# TurntableStrobeModule.net
KiCad netlist of a schematic drawn in EAGLE
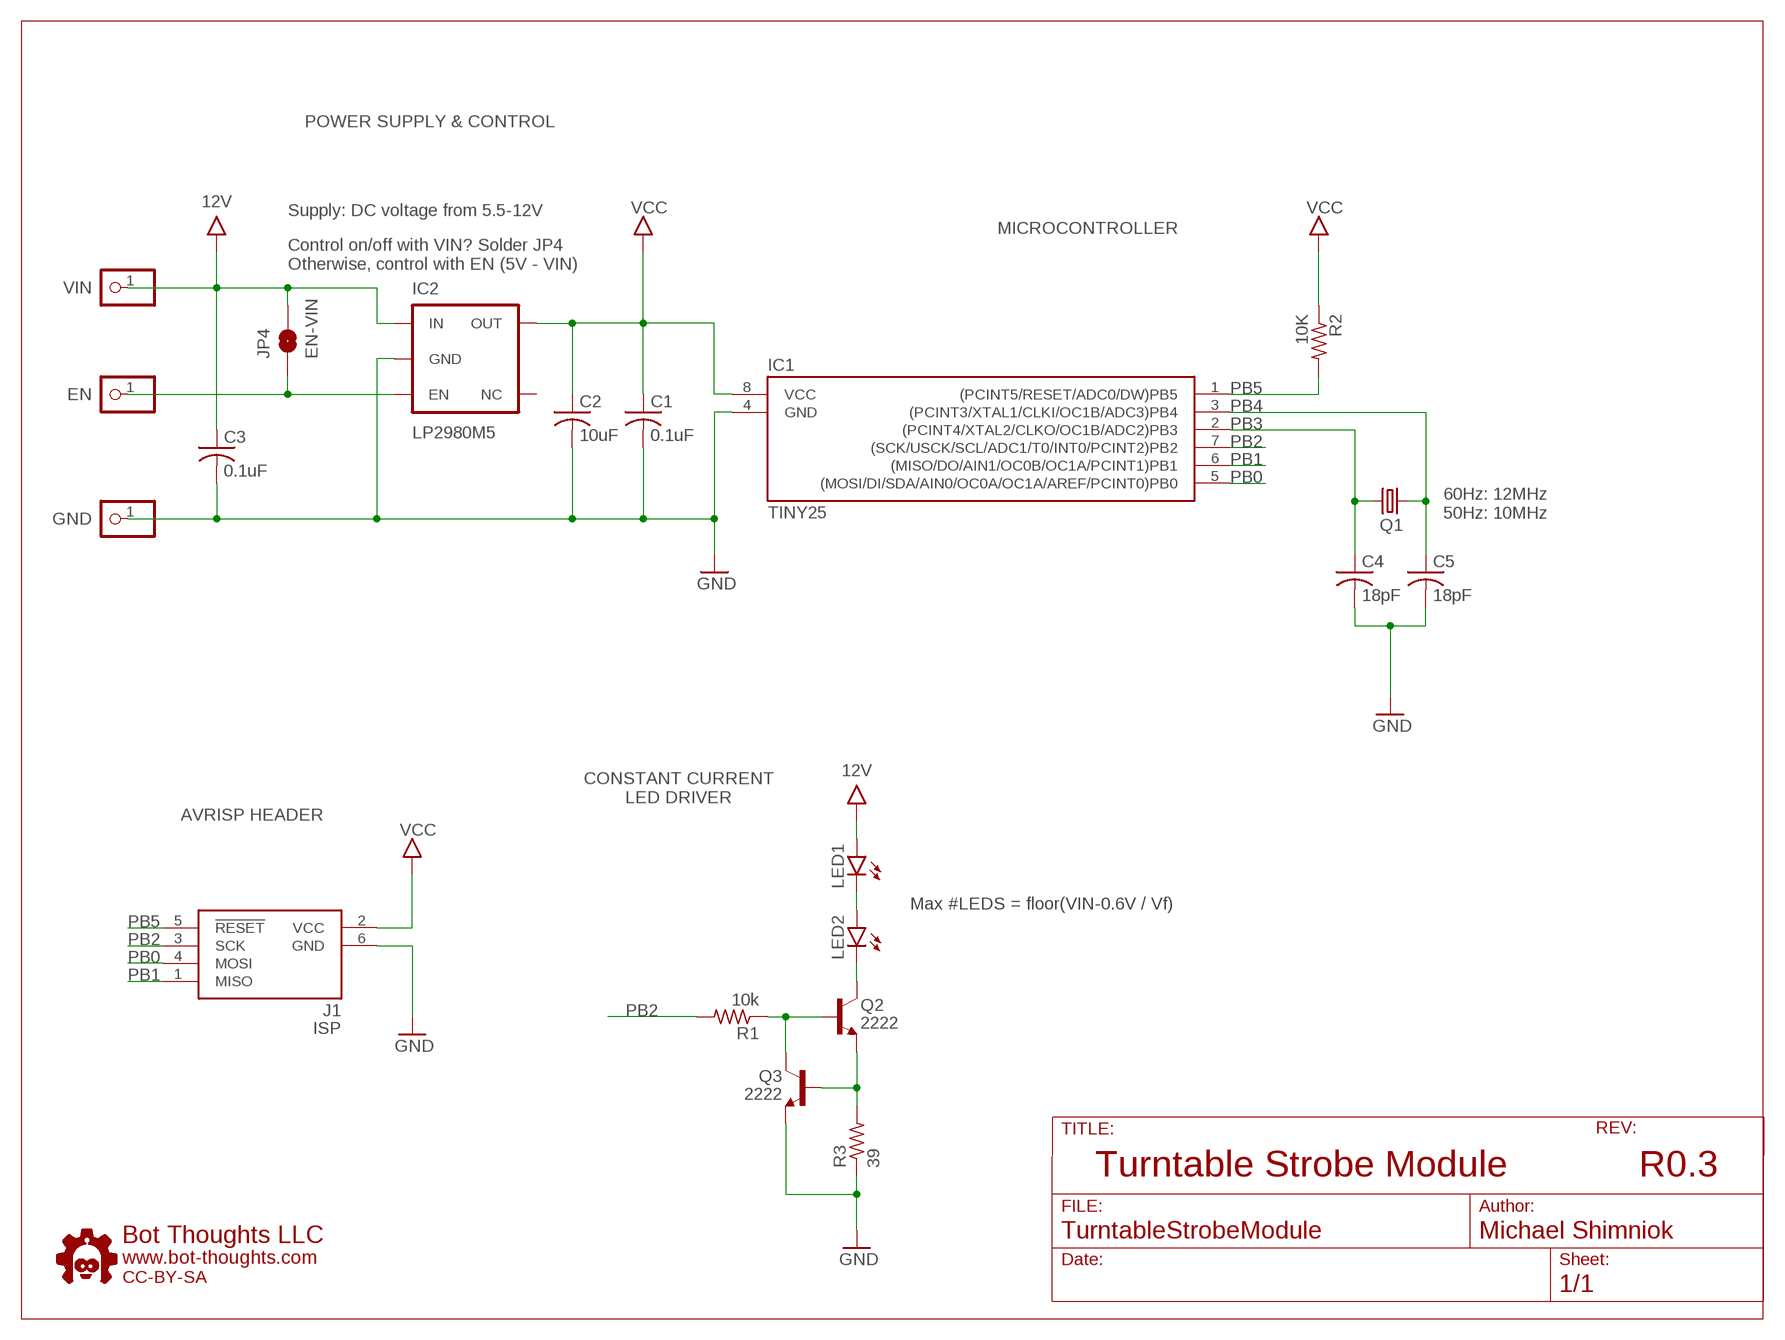
[diagram p0: schematic, sheet 1]

(export (version "E")
  (design (tool "Eeschema 10.0.6"))
  (components
    (comp (ref "C1")
      (value "0.1uF")
      (footprint "eagle-import:0603")
      (libsource (lib "eagle-import") (part "C-0603"))
    )
    (comp (ref "C2")
      (value "10uF")
      (footprint "eagle-import:1206")
      (libsource (lib "eagle-import") (part "C-1206"))
    )
    (comp (ref "C3")
      (value "0.1uF")
      (footprint "eagle-import:0603")
      (libsource (lib "eagle-import") (part "C-0603"))
    )
    (comp (ref "C4")
      (value "18pF")
      (footprint "eagle-import:0603")
      (libsource (lib "eagle-import") (part "C-0603"))
    )
    (comp (ref "C5")
      (value "18pF")
      (footprint "eagle-import:0603")
      (libsource (lib "eagle-import") (part "C-0603"))
    )
    (comp (ref "IC1")
      (value "TINY25")
      (footprint "eagle-import:SOIC8N")
      (libsource (lib "eagle-import") (part "TINY25/45/85-20SSU"))
    )
    (comp (ref "IC2")
      (value "LP2980M5")
      (footprint "eagle-import:SOT23-5")
      (libsource (lib "eagle-import") (part "LP2980M5"))
    )
    (comp (ref "J1")
      (value "ISP")
      (footprint "eagle-import:CON6P2R")
      (libsource (lib "eagle-import") (part "AVRISP6_COMPACT"))
    )
    (comp (ref "JP1")
      (value "EN")
      (footprint "eagle-import:1X01-S")
      (libsource (lib "eagle-import") (part "PINHD-1X01_2.54-S"))
    )
    (comp (ref "JP2")
      (value "VIN")
      (footprint "eagle-import:1X01-S")
      (libsource (lib "eagle-import") (part "PINHD-1X01_2.54-S"))
    )
    (comp (ref "JP3")
      (value "GND")
      (footprint "eagle-import:1X01-S")
      (libsource (lib "eagle-import") (part "PINHD-1X01_2.54-S"))
    )
    (comp (ref "JP4")
      (value "EN-VIN")
      (footprint "eagle-import:SMT-JUMPER_2_NO_SILK")
      (libsource (lib "eagle-import") (part "JUMPER-SMT_2_NO_SILK"))
    )
    (comp (ref "LED1")
      (value "LED5MMRA")
      (footprint "eagle-import:LED5MMRA")
      (libsource (lib "eagle-import") (part "LED5MMRA"))
    )
    (comp (ref "LED2")
      (value "LED5MMRA")
      (footprint "eagle-import:LED5MMRA")
      (libsource (lib "eagle-import") (part "LED5MMRA"))
    )
    (comp (ref "Q1")
      (value "CRYSTALNDK5X3")
      (footprint "eagle-import:NDK_2PAD_5X3")
      (libsource (lib "eagle-import") (part "CRYSTALNDK5X3"))
    )
    (comp (ref "Q2")
      (value "2222")
      (footprint "eagle-import:SOT-23")
      (libsource (lib "eagle-import") (part "BJT-NPNSOT23"))
    )
    (comp (ref "Q3")
      (value "2222")
      (footprint "eagle-import:SOT-23")
      (libsource (lib "eagle-import") (part "BJT-NPNSOT23"))
    )
    (comp (ref "R1")
      (value "10k")
      (footprint "eagle-import:0603")
      (libsource (lib "eagle-import") (part "R0603"))
    )
    (comp (ref "R2")
      (value "10K")
      (footprint "eagle-import:0603")
      (libsource (lib "eagle-import") (part "R0603"))
    )
    (comp (ref "R3")
      (value "39")
      (footprint "eagle-import:0603")
      (libsource (lib "eagle-import") (part "R0603"))
    )
    (comp (ref "U$6")
      (value "BTLOGO-LOGO-MD")
      (footprint "eagle-import:BTLOGOM")
      (libsource (lib "eagle-import") (part "BTLOGO-LOGO-MD"))
    )
  )
  (nets
    (net (code "1") (name "/PB0") (class "Default")
      (node (ref "IC1") (pin "5") (pinfunction "(MOSI/DI/SDA/AIN0/OC0A/OC1A/AREF/PCINT0)PB0_5") (pintype "bidirectional"))
      (node (ref "J1") (pin "4") (pinfunction "MOSI_4") (pintype "output"))
    )
    (net (code "2") (name "/PB1") (class "Default")
      (node (ref "IC1") (pin "6") (pinfunction "(MISO/DO/AIN1/OC0B/OC1A/PCINT1)PB1_6") (pintype "bidirectional"))
      (node (ref "J1") (pin "1") (pinfunction "MISO_1") (pintype "input"))
    )
    (net (code "3") (name "/PB2") (class "Default")
      (node (ref "IC1") (pin "7") (pinfunction "(SCK/USCK/SCL/ADC1/T0/INT0/PCINT2)PB2_7") (pintype "bidirectional"))
      (node (ref "J1") (pin "3") (pinfunction "SCK_3") (pintype "output"))
      (node (ref "R1") (pin "2") (pinfunction "2_2") (pintype "passive"))
    )
    (net (code "4") (name "/PB3") (class "Default")
      (node (ref "C4") (pin "1") (pinfunction "+_1") (pintype "passive"))
      (node (ref "IC1") (pin "2") (pinfunction "(PCINT4/XTAL2/CLKO/OC1B/ADC2)PB3_2") (pintype "bidirectional"))
      (node (ref "Q1") (pin "P$2") (pinfunction "2_P$2") (pintype "passive"))
    )
    (net (code "5") (name "/PB4") (class "Default")
      (node (ref "C5") (pin "1") (pinfunction "+_1") (pintype "passive"))
      (node (ref "IC1") (pin "3") (pinfunction "(PCINT3/XTAL1/CLKI/OC1B/ADC3)PB4_3") (pintype "bidirectional"))
      (node (ref "Q1") (pin "P$1") (pinfunction "1_P$1") (pintype "passive"))
    )
    (net (code "6") (name "/PB5") (class "Default")
      (node (ref "IC1") (pin "1") (pinfunction "(PCINT5/RESET/ADC0/DW)PB5_1") (pintype "bidirectional"))
      (node (ref "J1") (pin "5") (pinfunction "~{RESET}_5") (pintype "output"))
      (node (ref "R2") (pin "2") (pinfunction "2_2") (pintype "passive"))
    )
    (net (code "7") (name "12V") (class "Default")
      (node (ref "C3") (pin "1") (pinfunction "+_1") (pintype "passive"))
      (node (ref "IC2") (pin "1") (pinfunction "IN_1") (pintype "input"))
      (node (ref "JP2") (pin "1") (pinfunction "1_1") (pintype "passive"))
      (node (ref "JP4") (pin "2") (pinfunction "2_2") (pintype "passive"))
      (node (ref "LED1") (pin "A") (pinfunction "A_A") (pintype "passive"))
    )
    (net (code "8") (name "GND") (class "Default")
      (node (ref "C1") (pin "2") (pinfunction "-_2") (pintype "passive"))
      (node (ref "C2") (pin "2") (pinfunction "-_2") (pintype "passive"))
      (node (ref "C3") (pin "2") (pinfunction "-_2") (pintype "passive"))
      (node (ref "C4") (pin "2") (pinfunction "-_2") (pintype "passive"))
      (node (ref "C5") (pin "2") (pinfunction "-_2") (pintype "passive"))
      (node (ref "IC1") (pin "4") (pinfunction "GND_4") (pintype "power_in"))
      (node (ref "IC2") (pin "2") (pinfunction "GND_2") (pintype "input"))
      (node (ref "J1") (pin "6") (pinfunction "GND_6") (pintype "power_in"))
      (node (ref "JP3") (pin "1") (pinfunction "1_1") (pintype "passive"))
      (node (ref "Q3") (pin "2") (pinfunction "E_2") (pintype "passive"))
      (node (ref "R3") (pin "1") (pinfunction "1_1") (pintype "passive"))
    )
    (net (code "9") (name "Net-(IC2-EN)") (class "Default")
      (node (ref "IC2") (pin "3") (pinfunction "EN_3") (pintype "input"))
      (node (ref "JP1") (pin "1") (pinfunction "1_1") (pintype "passive"))
      (node (ref "JP4") (pin "1") (pinfunction "1_1") (pintype "passive"))
    )
    (net (code "10") (name "Net-(LED1-PadC)") (class "Default")
      (node (ref "LED1") (pin "C") (pinfunction "C_C") (pintype "passive"))
      (node (ref "LED2") (pin "A") (pinfunction "A_A") (pintype "passive"))
    )
    (net (code "11") (name "Net-(Q2-B)") (class "Default")
      (node (ref "Q2") (pin "3") (pinfunction "B_3") (pintype "passive"))
      (node (ref "Q3") (pin "1") (pinfunction "C_1") (pintype "passive"))
      (node (ref "R1") (pin "1") (pinfunction "1_1") (pintype "passive"))
    )
    (net (code "12") (name "Net-(Q2-C)") (class "Default")
      (node (ref "LED2") (pin "C") (pinfunction "C_C") (pintype "passive"))
      (node (ref "Q2") (pin "1") (pinfunction "C_1") (pintype "passive"))
    )
    (net (code "13") (name "Net-(Q2-E)") (class "Default")
      (node (ref "Q2") (pin "2") (pinfunction "E_2") (pintype "passive"))
      (node (ref "Q3") (pin "3") (pinfunction "B_3") (pintype "passive"))
      (node (ref "R3") (pin "2") (pinfunction "2_2") (pintype "passive"))
    )
    (net (code "14") (name "VCC") (class "Default")
      (node (ref "C1") (pin "1") (pinfunction "+_1") (pintype "passive"))
      (node (ref "C2") (pin "1") (pinfunction "+_1") (pintype "passive"))
      (node (ref "IC1") (pin "8") (pinfunction "VCC_8") (pintype "power_in"))
      (node (ref "IC2") (pin "5") (pinfunction "OUT_5") (pintype "passive"))
      (node (ref "J1") (pin "2") (pinfunction "VCC_2") (pintype "power_in"))
      (node (ref "R2") (pin "1") (pinfunction "1_1") (pintype "passive"))
    )
    (net (code "15") (name "unconnected-(IC2-NC-Pad4)") (class "Default")
      (node (ref "IC2") (pin "4") (pinfunction "NC_4") (pintype "no_connect"))
    )
  )
)
